# power.net
KiCad netlist of a schematic drawn in Altium Designer
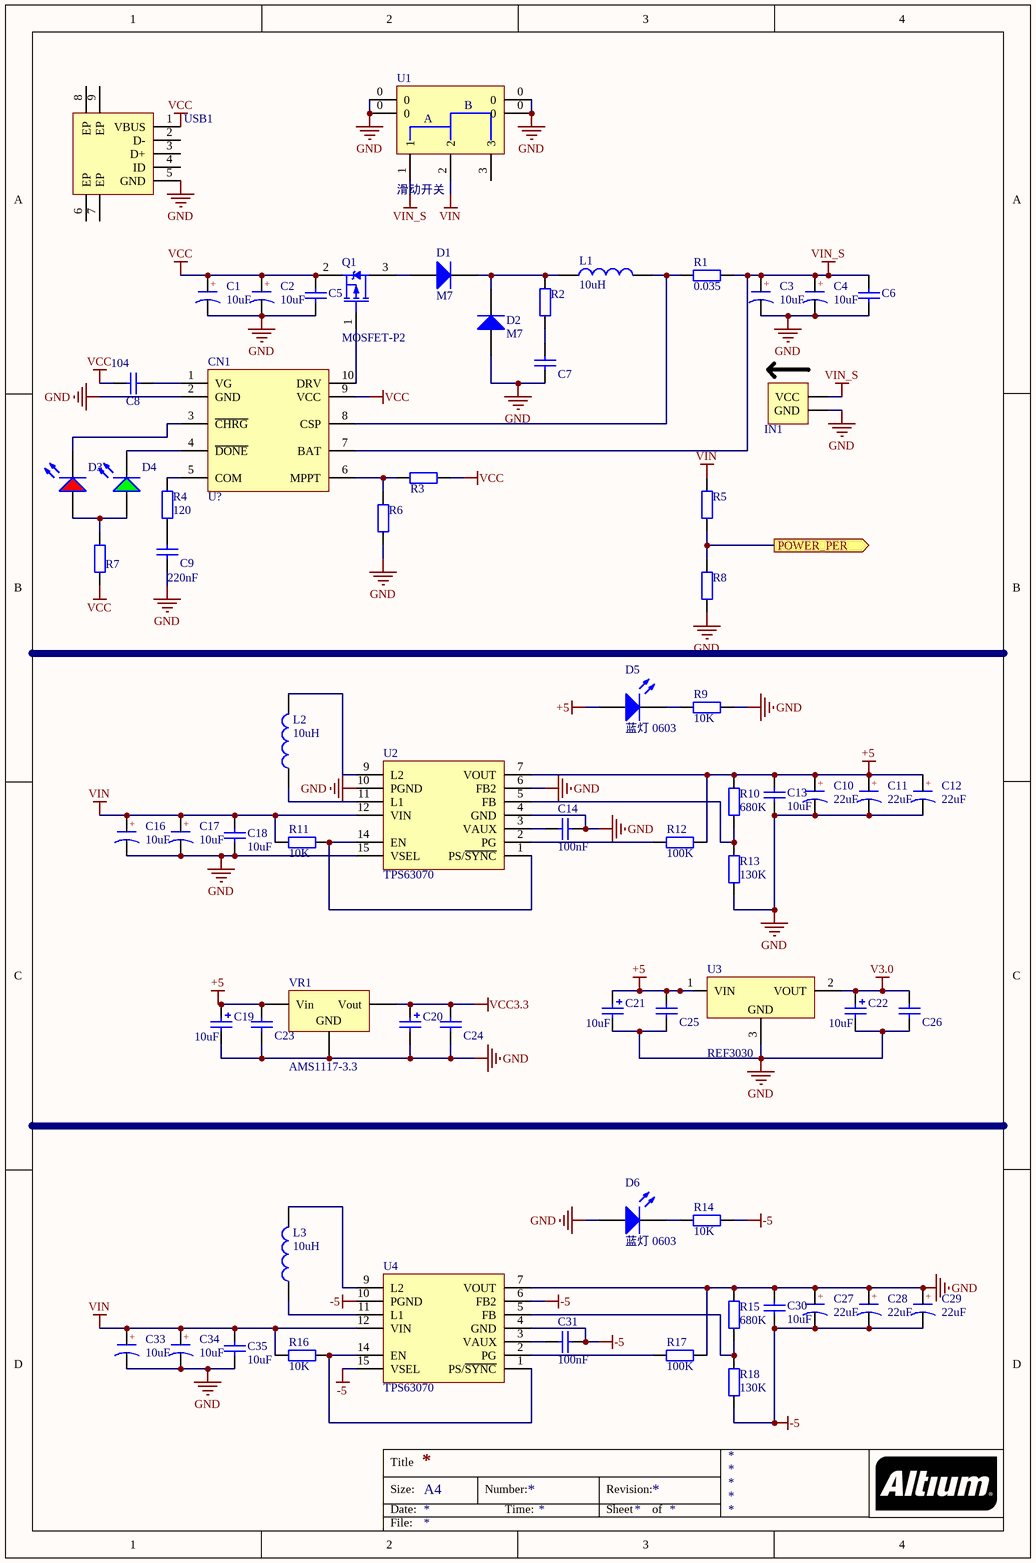
[diagram p0: power.SchDoc]

(export (version "E")
  (design (tool "Eeschema 10.0.6"))
  (components
    (comp (ref "C1")
      (value "10uF")
      (footprint "226C")
      (description "贴片钽电容")
      (fields (field (name "Comment") "CAP+"))
      (libsource (lib "Cooperation") (part "0CAP+"))
    )
    (comp (ref "C2")
      (value "10uF")
      (footprint "226C")
      (description "贴片钽电容")
      (fields (field (name "Comment") "CAP+"))
      (libsource (lib "Cooperation") (part "0CAP+"))
    )
    (comp (ref "C3")
      (value "10uF")
      (footprint "226C")
      (description "贴片钽电容")
      (fields (field (name "Comment") "CAP+"))
      (libsource (lib "Cooperation") (part "0CAP+"))
    )
    (comp (ref "C4")
      (value "10uF")
      (footprint "226C")
      (description "贴片钽电容")
      (fields (field (name "Comment") "CAP+"))
      (libsource (lib "Cooperation") (part "0CAP+"))
    )
    (comp (ref "C5")
      (value "10nF (103) 10% 50V")
      (footprint "0603_C")
      (description "贴片电容")
      (libsource (lib "JLC") (part "0603 10nF (103) 10% 50V"))
    )
    (comp (ref "C6")
      (value "10nF (103) 10% 50V")
      (footprint "0603_C")
      (description "贴片电容")
      (libsource (lib "JLC") (part "0603 10nF (103) 10% 50V"))
    )
    (comp (ref "C7")
      (value "10nF (103) 10% 50V")
      (footprint "0603_C")
      (description "贴片电容")
      (libsource (lib "JLC") (part "0603 10nF (103) 10% 50V"))
    )
    (comp (ref "C8")
      (value "104")
      (footprint "0603_C")
      (description "贴片电容")
      (libsource (lib "JLC") (part "0603 10nF (103) 10% 50V"))
    )
    (comp (ref "C9")
      (value "220nF")
      (footprint "0603_C")
      (description "贴片电容")
      (libsource (lib "JLC") (part "0603 10nF (103) 10% 50V"))
    )
    (comp (ref "C10")
      (value "22uF")
      (footprint "226C")
      (description "贴片钽电容")
      (fields (field (name "Comment") "CAP+"))
      (libsource (lib "Cooperation") (part "0CAP+"))
    )
    (comp (ref "C11")
      (value "22uF")
      (footprint "226C")
      (description "贴片钽电容")
      (fields (field (name "Comment") "CAP+"))
      (libsource (lib "Cooperation") (part "0CAP+"))
    )
    (comp (ref "C12")
      (value "22uF")
      (footprint "226C")
      (description "贴片钽电容")
      (fields (field (name "Comment") "CAP+"))
      (libsource (lib "Cooperation") (part "0CAP+"))
    )
    (comp (ref "C13")
      (value "10uF")
      (footprint "0603_C")
      (description "贴片电容")
      (libsource (lib "JLC") (part "0603 10uF (106) 10% 10V"))
    )
    (comp (ref "C14")
      (value "100nF")
      (footprint "0603_C")
      (description "贴片电容")
      (libsource (lib "JLC") (part "0603 10uF (106) 10% 10V"))
    )
    (comp (ref "C16")
      (value "10uF")
      (footprint "226C")
      (description "贴片钽电容")
      (fields (field (name "Comment") "CAP+"))
      (libsource (lib "Cooperation") (part "0CAP+"))
    )
    (comp (ref "C17")
      (value "10uF")
      (footprint "226C")
      (description "贴片钽电容")
      (fields (field (name "Comment") "CAP+"))
      (libsource (lib "Cooperation") (part "0CAP+"))
    )
    (comp (ref "C18")
      (value "10uF")
      (footprint "0603_C")
      (description "贴片电容")
      (libsource (lib "JLC") (part "0603 10uF (106) 10% 10V"))
    )
    (comp (ref "C19")
      (value "10uF")
      (footprint "CASE-A_3216")
      (description "钽电容")
      (libsource (lib "JLC") (part "3216 10uF (106) 10% 16V"))
    )
    (comp (ref "C20")
      (value "10uF (106) ±10% 16V")
      (footprint "CASE-A_3216")
      (description "钽电容")
      (libsource (lib "JLC") (part "3216 10uF (106) 10% 16V"))
    )
    (comp (ref "C21")
      (value "10uF")
      (footprint "CASE-A_3216")
      (description "钽电容")
      (libsource (lib "JLC") (part "3216 10uF (106) 10% 16V"))
    )
    (comp (ref "C22")
      (value "10uF")
      (footprint "CASE-A_3216")
      (description "钽电容")
      (libsource (lib "JLC") (part "3216 10uF (106) 10% 16V"))
    )
    (comp (ref "C23")
      (value "100nF (104) 10% 50V")
      (footprint "0603_C")
      (description "贴片电容")
      (libsource (lib "JLC") (part "0603 100nF (104) 10% 50V"))
    )
    (comp (ref "C24")
      (value "100nF (104) 10% 50V")
      (footprint "0603_C")
      (description "贴片电容")
      (libsource (lib "JLC") (part "0603 100nF (104) 10% 50V"))
    )
    (comp (ref "C25")
      (value "100nF (104) 10% 50V")
      (footprint "0603_C")
      (description "贴片电容")
      (libsource (lib "JLC") (part "0603 100nF (104) 10% 50V"))
    )
    (comp (ref "C26")
      (value "100nF (104) 10% 50V")
      (footprint "0603_C")
      (description "贴片电容")
      (libsource (lib "JLC") (part "0603 100nF (104) 10% 50V"))
    )
    (comp (ref "C27")
      (value "22uF")
      (footprint "226C")
      (description "贴片钽电容")
      (fields (field (name "Comment") "CAP+"))
      (libsource (lib "Cooperation") (part "0CAP+"))
    )
    (comp (ref "C28")
      (value "22uF")
      (footprint "226C")
      (description "贴片钽电容")
      (fields (field (name "Comment") "CAP+"))
      (libsource (lib "Cooperation") (part "0CAP+"))
    )
    (comp (ref "C29")
      (value "22uF")
      (footprint "226C")
      (description "贴片钽电容")
      (fields (field (name "Comment") "CAP+"))
      (libsource (lib "Cooperation") (part "0CAP+"))
    )
    (comp (ref "C30")
      (value "10uF")
      (footprint "0603_C")
      (description "贴片电容")
      (libsource (lib "JLC") (part "0603 10uF (106) 10% 10V"))
    )
    (comp (ref "C31")
      (value "100nF")
      (footprint "0603_C")
      (description "贴片电容")
      (libsource (lib "JLC") (part "0603 10uF (106) 10% 10V"))
    )
    (comp (ref "C33")
      (value "10uF")
      (footprint "226C")
      (description "贴片钽电容")
      (fields (field (name "Comment") "CAP+"))
      (libsource (lib "Cooperation") (part "0CAP+"))
    )
    (comp (ref "C34")
      (value "10uF")
      (footprint "226C")
      (description "贴片钽电容")
      (fields (field (name "Comment") "CAP+"))
      (libsource (lib "Cooperation") (part "0CAP+"))
    )
    (comp (ref "C35")
      (value "10uF")
      (footprint "0603_C")
      (description "贴片电容")
      (libsource (lib "JLC") (part "0603 10uF (106) 10% 10V"))
    )
    (comp (ref "CN1") (value "U?") (footprint "SSOP_10") (libsource (lib "Cooperation") (part "CN3791")))
    (comp (ref "D1")
      (value "M7")
      (footprint "SMA(DO-214AC)_S1")
      (description "二极管")
      (libsource (lib "JLC") (part "SMA(DO-214AC) M7"))
    )
    (comp (ref "D2")
      (value "M7")
      (footprint "SMA(DO-214AC)_S1")
      (description "二极管")
      (libsource (lib "JLC") (part "SMA(DO-214AC) M7"))
    )
    (comp (ref "D3")
      (value "红灯 0603")
      (footprint "0603_LED_S1")
      (description "发光二极管")
      (libsource (lib "JLC") (part "0603 红灯"))
    )
    (comp (ref "D4")
      (value "绿灯 0603")
      (footprint "0603_LED_S1")
      (description "发光二极管")
      (libsource (lib "JLC") (part "0603 绿灯"))
    )
    (comp (ref "D5")
      (value "蓝灯 0603")
      (footprint "0603_LED_S1")
      (description "发光二极管")
      (libsource (lib "JLC") (part "0603 蓝灯"))
    )
    (comp (ref "D6")
      (value "蓝灯 0603")
      (footprint "0603_LED_S1")
      (description "发光二极管")
      (libsource (lib "JLC") (part "0603 蓝灯"))
    )
    (comp (ref "IN1")
      (value "HDR-1X2")
      (footprint "Power_IN_3.81-2P")
      (description "2P接插件,模块单电源供电口")
      (fields (field (name "版权归属") "源创客"))
      (libsource (lib "Cooperation") (part "PORT_Power_IN2"))
    )
    (comp (ref "L1")
      (value "10uH")
      (footprint "L8*8*4")
      (description "小功率贴片电感")
      (fields (field (name "Comment") "IND"))
      (libsource (lib "Cooperation") (part "0IND"))
    )
    (comp (ref "L2")
      (value "10uH")
      (footprint "L_6*6*2")
      (description "小功率贴片电感")
      (fields (field (name "Comment") "IND"))
      (libsource (lib "Cooperation") (part "0IND"))
    )
    (comp (ref "L3")
      (value "10uH")
      (footprint "L_6*6*2")
      (description "小功率贴片电感")
      (fields (field (name "Comment") "IND"))
      (libsource (lib "Cooperation") (part "0IND"))
    )
    (comp (ref "Q1")
      (value "MOSFET-P2")
      (footprint "SOT23-3M")
      (description "P-Channel MOSFET")
      (fields (field (name "PUBLISHER") "Altium Limited"))
      (libsource (lib "Cooperation") (part "MOS_MOSFET-P2"))
    )
    (comp (ref "R1")
      (value "0.035")
      (footprint "R 2512_L")
      (description "贴片电阻")
      (libsource (lib "") (part "0603 100Ω (1000) 1%_1"))
    )
    (comp (ref "R2")
      (value "100Ω (1000) ±1%")
      (footprint "0603_R")
      (description "贴片电阻")
      (libsource (lib "JLC") (part "0603 100Ω (1000) 1%"))
    )
    (comp (ref "R3")
      (value "100Ω (1000) ±1%")
      (footprint "0603_R")
      (description "贴片电阻")
      (libsource (lib "") (part "0603 100Ω (1000) 1%_1"))
    )
    (comp (ref "R4")
      (value "120")
      (footprint "0603_R")
      (description "贴片电阻")
      (libsource (lib "JLC") (part "0603 100Ω (1000) 1%"))
    )
    (comp (ref "R5")
      (value "100Ω (1000) ±1%")
      (footprint "0603_R")
      (description "贴片电阻")
      (libsource (lib "JLC") (part "0603 100Ω (1000) 1%"))
    )
    (comp (ref "R6")
      (value "100Ω (1000) ±1%")
      (footprint "0603_R")
      (description "贴片电阻")
      (libsource (lib "JLC") (part "0603 100Ω (1000) 1%"))
    )
    (comp (ref "R7")
      (value "100Ω (1000) ±1%")
      (footprint "0603_R")
      (description "贴片电阻")
      (libsource (lib "") (part "0603 100Ω (1000) 1%_2"))
    )
    (comp (ref "R8")
      (value "100Ω (1000) ±1%")
      (footprint "0603_R")
      (description "贴片电阻")
      (libsource (lib "JLC") (part "0603 100Ω (1000) 1%"))
    )
    (comp (ref "R9")
      (value "10K")
      (footprint "0603_R")
      (description "贴片电阻")
      (libsource (lib "JLC") (part "0603 1.2KΩ (1201) 1%"))
    )
    (comp (ref "R10")
      (value "680K")
      (footprint "0603_R")
      (description "贴片电阻")
      (libsource (lib "") (part "0603 1.2KΩ (1201) 1%_1"))
    )
    (comp (ref "R11")
      (value "10K")
      (footprint "0603_R")
      (description "贴片电阻")
      (libsource (lib "JLC") (part "0603 1.2KΩ (1201) 1%"))
    )
    (comp (ref "R12")
      (value "100K")
      (footprint "0603_R")
      (description "贴片电阻")
      (libsource (lib "") (part "0603 1.2KΩ (1201) 1%_2"))
    )
    (comp (ref "R13")
      (value "130K")
      (footprint "0603_R")
      (description "贴片电阻")
      (libsource (lib "") (part "0603 1.2KΩ (1201) 1%_1"))
    )
    (comp (ref "R14")
      (value "10K")
      (footprint "0603_R")
      (description "贴片电阻")
      (libsource (lib "JLC") (part "0603 1.2KΩ (1201) 1%"))
    )
    (comp (ref "R15")
      (value "680K")
      (footprint "0603_R")
      (description "贴片电阻")
      (libsource (lib "") (part "0603 1.2KΩ (1201) 1%_1"))
    )
    (comp (ref "R16")
      (value "10K")
      (footprint "0603_R")
      (description "贴片电阻")
      (libsource (lib "JLC") (part "0603 1.2KΩ (1201) 1%"))
    )
    (comp (ref "R17")
      (value "100K")
      (footprint "0603_R")
      (description "贴片电阻")
      (libsource (lib "") (part "0603 1.2KΩ (1201) 1%_2"))
    )
    (comp (ref "R18")
      (value "130K")
      (footprint "0603_R")
      (description "贴片电阻")
      (libsource (lib "") (part "0603 1.2KΩ (1201) 1%_1"))
    )
    (comp (ref "U1")
      (value "滑动开关")
      (footprint "SW-SMD_3P-L6.6-W2.7-P1.50 - duplicate")
      (libsource (lib "Cooperation") (part "TA_6.6*2.7*2.5_滑动开关"))
    )
    (comp (ref "U2")
      (value "TPS63070")
      (footprint "TPS63070")
      (libsource (lib "Cooperation") (part "TPS63070"))
    )
    (comp (ref "U3")
      (value "REF3030")
      (footprint "SOT23-3N")
      (libsource (lib "Cooperation") (part "REF3040"))
    )
    (comp (ref "U4")
      (value "TPS63070")
      (footprint "TPS63070")
      (libsource (lib "Cooperation") (part "TPS63070"))
    )
    (comp (ref "USB1")
      (value "PORT_micro-5P破板式")
      (footprint "micro-5P破板式")
      (libsource (lib "Cooperation") (part "PORT_micro-5P破板式"))
    )
    (comp (ref "VR1")
      (value "AMS1117-3.3")
      (footprint "SOT-223")
      (description "低压差线性稳压(LDO)")
      (libsource (lib "JLC") (part "SOT-223 AMS1117-3.3"))
    )
  )
  (nets
    (net (code "1") (name "+5") (class "Default")
      (node (ref "C10") (pin "1") (pinfunction "A_1") (pintype "passive"))
      (node (ref "C11") (pin "1") (pinfunction "A_1") (pintype "passive"))
      (node (ref "C12") (pin "1") (pinfunction "A_1") (pintype "passive"))
      (node (ref "C13") (pin "2") (pinfunction "2_2") (pintype "passive"))
      (node (ref "C19") (pin "1") (pinfunction "1_1") (pintype "passive"))
      (node (ref "C21") (pin "1") (pinfunction "1_1") (pintype "passive"))
      (node (ref "C23") (pin "1") (pinfunction "1_1") (pintype "passive"))
      (node (ref "C25") (pin "1") (pinfunction "1_1") (pintype "passive"))
      (node (ref "D5") (pin "A") (pinfunction "A_A") (pintype "passive"))
      (node (ref "R10") (pin "2") (pinfunction "2_2") (pintype "passive"))
      (node (ref "R12") (pin "1") (pinfunction "1_1") (pintype "passive"))
      (node (ref "U2") (pin "7") (pinfunction "VOUT_7") (pintype "passive"))
      (node (ref "U3") (pin "1") (pinfunction "VIN_1") (pintype "passive"))
      (node (ref "VR1") (pin "3") (pinfunction "Vin_3") (pintype "passive"))
    )
    (net (code "2") (name "-5") (class "Default")
      (node (ref "C27") (pin "2") (pinfunction "K_2") (pintype "passive"))
      (node (ref "C28") (pin "2") (pinfunction "K_2") (pintype "passive"))
      (node (ref "C29") (pin "2") (pinfunction "K_2") (pintype "passive"))
      (node (ref "C30") (pin "1") (pinfunction "1_1") (pintype "passive"))
      (node (ref "C31") (pin "1") (pinfunction "1_1") (pintype "passive"))
      (node (ref "R14") (pin "2") (pinfunction "2_2") (pintype "passive"))
      (node (ref "R18") (pin "1") (pinfunction "1_1") (pintype "passive"))
      (node (ref "U4") (pin "10") (pinfunction "PGND_10") (pintype "passive"))
      (node (ref "U4") (pin "15") (pinfunction "VSEL_15") (pintype "passive"))
      (node (ref "U4") (pin "4") (pinfunction "GND_4") (pintype "passive"))
      (node (ref "U4") (pin "6") (pinfunction "FB2_6") (pintype "passive"))
    )
    (net (code "3") (name "/POWER_PER") (class "Default")
      (node (ref "R5") (pin "1") (pinfunction "1_1") (pintype "passive"))
      (node (ref "R8") (pin "2") (pinfunction "2_2") (pintype "passive"))
    )
    (net (code "4") (name "GND") (class "Default")
      (node (ref "C1") (pin "2") (pinfunction "K_2") (pintype "passive"))
      (node (ref "C10") (pin "2") (pinfunction "K_2") (pintype "passive"))
      (node (ref "C11") (pin "2") (pinfunction "K_2") (pintype "passive"))
      (node (ref "C12") (pin "2") (pinfunction "K_2") (pintype "passive"))
      (node (ref "C13") (pin "1") (pinfunction "1_1") (pintype "passive"))
      (node (ref "C14") (pin "1") (pinfunction "1_1") (pintype "passive"))
      (node (ref "C16") (pin "2") (pinfunction "K_2") (pintype "passive"))
      (node (ref "C17") (pin "2") (pinfunction "K_2") (pintype "passive"))
      (node (ref "C18") (pin "1") (pinfunction "1_1") (pintype "passive"))
      (node (ref "C19") (pin "2") (pinfunction "2_2") (pintype "passive"))
      (node (ref "C2") (pin "2") (pinfunction "K_2") (pintype "passive"))
      (node (ref "C20") (pin "2") (pinfunction "2_2") (pintype "passive"))
      (node (ref "C21") (pin "2") (pinfunction "2_2") (pintype "passive"))
      (node (ref "C22") (pin "2") (pinfunction "2_2") (pintype "passive"))
      (node (ref "C23") (pin "2") (pinfunction "2_2") (pintype "passive"))
      (node (ref "C24") (pin "2") (pinfunction "2_2") (pintype "passive"))
      (node (ref "C25") (pin "2") (pinfunction "2_2") (pintype "passive"))
      (node (ref "C26") (pin "2") (pinfunction "2_2") (pintype "passive"))
      (node (ref "C27") (pin "1") (pinfunction "A_1") (pintype "passive"))
      (node (ref "C28") (pin "1") (pinfunction "A_1") (pintype "passive"))
      (node (ref "C29") (pin "1") (pinfunction "A_1") (pintype "passive"))
      (node (ref "C3") (pin "2") (pinfunction "K_2") (pintype "passive"))
      (node (ref "C30") (pin "2") (pinfunction "2_2") (pintype "passive"))
      (node (ref "C33") (pin "2") (pinfunction "K_2") (pintype "passive"))
      (node (ref "C34") (pin "2") (pinfunction "K_2") (pintype "passive"))
      (node (ref "C35") (pin "1") (pinfunction "1_1") (pintype "passive"))
      (node (ref "C4") (pin "2") (pinfunction "K_2") (pintype "passive"))
      (node (ref "C5") (pin "1") (pinfunction "1_1") (pintype "passive"))
      (node (ref "C6") (pin "1") (pinfunction "1_1") (pintype "passive"))
      (node (ref "C7") (pin "2") (pinfunction "2_2") (pintype "passive"))
      (node (ref "C9") (pin "2") (pinfunction "2_2") (pintype "passive"))
      (node (ref "CN1") (pin "2") (pinfunction "GND_2") (pintype "passive"))
      (node (ref "D2") (pin "1") (pinfunction "A_1") (pintype "passive"))
      (node (ref "D6") (pin "A") (pinfunction "A_A") (pintype "passive"))
      (node (ref "IN1") (pin "2") (pinfunction "GND_2") (pintype "passive"))
      (node (ref "R13") (pin "1") (pinfunction "1_1") (pintype "passive"))
      (node (ref "R15") (pin "2") (pinfunction "2_2") (pintype "passive"))
      (node (ref "R17") (pin "1") (pinfunction "1_1") (pintype "passive"))
      (node (ref "R6") (pin "1") (pinfunction "1_1") (pintype "passive"))
      (node (ref "R8") (pin "1") (pinfunction "1_1") (pintype "passive"))
      (node (ref "R9") (pin "2") (pinfunction "2_2") (pintype "passive"))
      (node (ref "U1") (pin "0") (pinfunction "0_0") (pintype "passive"))
      (node (ref "U2") (pin "10") (pinfunction "PGND_10") (pintype "passive"))
      (node (ref "U2") (pin "15") (pinfunction "VSEL_15") (pintype "passive"))
      (node (ref "U2") (pin "4") (pinfunction "GND_4") (pintype "passive"))
      (node (ref "U2") (pin "6") (pinfunction "FB2_6") (pintype "passive"))
      (node (ref "U3") (pin "3") (pinfunction "GND_3") (pintype "passive"))
      (node (ref "U4") (pin "7") (pinfunction "VOUT_7") (pintype "passive"))
      (node (ref "USB1") (pin "5") (pinfunction "GND_5") (pintype "passive"))
      (node (ref "VR1") (pin "1") (pinfunction "GND_1") (pintype "passive"))
    )
    (net (code "5") (name "Net-(C7-Pad1)") (class "Default")
      (node (ref "C7") (pin "1") (pinfunction "1_1") (pintype "passive"))
      (node (ref "R2") (pin "1") (pinfunction "1_1") (pintype "passive"))
    )
    (net (code "6") (name "Net-(C9-Pad1)") (class "Default")
      (node (ref "C9") (pin "1") (pinfunction "1_1") (pintype "passive"))
      (node (ref "R4") (pin "1") (pinfunction "1_1") (pintype "passive"))
    )
    (net (code "7") (name "Net-(CN1-COM)") (class "Default")
      (node (ref "CN1") (pin "5") (pinfunction "COM_5") (pintype "passive"))
      (node (ref "R4") (pin "2") (pinfunction "2_2") (pintype "passive"))
    )
    (net (code "8") (name "Net-(CN1-CSP)") (class "Default")
      (node (ref "CN1") (pin "8") (pinfunction "CSP_8") (pintype "passive"))
      (node (ref "L1") (pin "2") (pinfunction "2_2") (pintype "passive"))
      (node (ref "R1") (pin "2") (pinfunction "2_2") (pintype "passive"))
    )
    (net (code "9") (name "Net-(CN1-DRV)") (class "Default")
      (node (ref "CN1") (pin "10") (pinfunction "DRV_10") (pintype "passive"))
      (node (ref "Q1") (pin "1") (pinfunction "G_1") (pintype "passive"))
    )
    (net (code "10") (name "Net-(CN1-MPPT)") (class "Default")
      (node (ref "CN1") (pin "6") (pinfunction "MPPT_6") (pintype "passive"))
      (node (ref "R3") (pin "2") (pinfunction "2_2") (pintype "passive"))
      (node (ref "R6") (pin "2") (pinfunction "2_2") (pintype "passive"))
    )
    (net (code "11") (name "Net-(CN1-VG)") (class "Default")
      (node (ref "C8") (pin "1") (pinfunction "1_1") (pintype "passive"))
      (node (ref "CN1") (pin "1") (pinfunction "VG_1") (pintype "passive"))
    )
    (net (code "12") (name "Net-(CN1-~{CHRG})") (class "Default")
      (node (ref "CN1") (pin "3") (pinfunction "~{CHRG}_3") (pintype "passive"))
      (node (ref "D3") (pin "K") (pinfunction "K_K") (pintype "passive"))
    )
    (net (code "13") (name "Net-(CN1-~{DONE})") (class "Default")
      (node (ref "CN1") (pin "4") (pinfunction "~{DONE}_4") (pintype "passive"))
      (node (ref "D4") (pin "K") (pinfunction "K_K") (pintype "passive"))
    )
    (net (code "14") (name "Net-(D1-A)") (class "Default")
      (node (ref "D1") (pin "1") (pinfunction "A_1") (pintype "passive"))
      (node (ref "Q1") (pin "3") (pinfunction "D_3") (pintype "passive"))
    )
    (net (code "15") (name "Net-(D1-K)") (class "Default")
      (node (ref "D1") (pin "2") (pinfunction "K_2") (pintype "passive"))
      (node (ref "D2") (pin "2") (pinfunction "K_2") (pintype "passive"))
      (node (ref "L1") (pin "1") (pinfunction "1_1") (pintype "passive"))
      (node (ref "R2") (pin "2") (pinfunction "2_2") (pintype "passive"))
    )
    (net (code "16") (name "Net-(D3-PadA)") (class "Default")
      (node (ref "D3") (pin "A") (pinfunction "A_A") (pintype "passive"))
      (node (ref "D4") (pin "A") (pinfunction "A_A") (pintype "passive"))
      (node (ref "R7") (pin "1") (pinfunction "1_1") (pintype "passive"))
    )
    (net (code "17") (name "Net-(D5-PadK)") (class "Default")
      (node (ref "D5") (pin "K") (pinfunction "K_K") (pintype "passive"))
      (node (ref "R9") (pin "1") (pinfunction "1_1") (pintype "passive"))
    )
    (net (code "18") (name "Net-(D6-PadK)") (class "Default")
      (node (ref "D6") (pin "K") (pinfunction "K_K") (pintype "passive"))
      (node (ref "R14") (pin "1") (pinfunction "1_1") (pintype "passive"))
    )
    (net (code "19") (name "Net-(U2-EN)") (class "Default")
      (node (ref "R11") (pin "2") (pinfunction "2_2") (pintype "passive"))
      (node (ref "U2") (pin "1") (pinfunction "PS/~{SYNC}_1") (pintype "passive"))
      (node (ref "U2") (pin "14") (pinfunction "EN_14") (pintype "passive"))
    )
    (net (code "20") (name "Net-(U2-FB)") (class "Default")
      (node (ref "R10") (pin "1") (pinfunction "1_1") (pintype "passive"))
      (node (ref "R13") (pin "2") (pinfunction "2_2") (pintype "passive"))
      (node (ref "U2") (pin "5") (pinfunction "FB_5") (pintype "passive"))
    )
    (net (code "21") (name "Net-(U2-L1)") (class "Default")
      (node (ref "L2") (pin "1") (pinfunction "1_1") (pintype "passive"))
      (node (ref "U2") (pin "11") (pinfunction "L1_11") (pintype "passive"))
    )
    (net (code "22") (name "Net-(U2-L2)") (class "Default")
      (node (ref "L2") (pin "2") (pinfunction "2_2") (pintype "passive"))
      (node (ref "U2") (pin "9") (pinfunction "L2_9") (pintype "passive"))
    )
    (net (code "23") (name "Net-(U2-PG)") (class "Default")
      (node (ref "R12") (pin "2") (pinfunction "2_2") (pintype "passive"))
      (node (ref "U2") (pin "2") (pinfunction "PG_2") (pintype "passive"))
    )
    (net (code "24") (name "Net-(U2-VAUX)") (class "Default")
      (node (ref "C14") (pin "2") (pinfunction "2_2") (pintype "passive"))
      (node (ref "U2") (pin "3") (pinfunction "VAUX_3") (pintype "passive"))
    )
    (net (code "25") (name "Net-(U4-EN)") (class "Default")
      (node (ref "R16") (pin "2") (pinfunction "2_2") (pintype "passive"))
      (node (ref "U4") (pin "1") (pinfunction "PS/~{SYNC}_1") (pintype "passive"))
      (node (ref "U4") (pin "14") (pinfunction "EN_14") (pintype "passive"))
    )
    (net (code "26") (name "Net-(U4-FB)") (class "Default")
      (node (ref "R15") (pin "1") (pinfunction "1_1") (pintype "passive"))
      (node (ref "R18") (pin "2") (pinfunction "2_2") (pintype "passive"))
      (node (ref "U4") (pin "5") (pinfunction "FB_5") (pintype "passive"))
    )
    (net (code "27") (name "Net-(U4-L1)") (class "Default")
      (node (ref "L3") (pin "1") (pinfunction "1_1") (pintype "passive"))
      (node (ref "U4") (pin "11") (pinfunction "L1_11") (pintype "passive"))
    )
    (net (code "28") (name "Net-(U4-L2)") (class "Default")
      (node (ref "L3") (pin "2") (pinfunction "2_2") (pintype "passive"))
      (node (ref "U4") (pin "9") (pinfunction "L2_9") (pintype "passive"))
    )
    (net (code "29") (name "Net-(U4-PG)") (class "Default")
      (node (ref "R17") (pin "2") (pinfunction "2_2") (pintype "passive"))
      (node (ref "U4") (pin "2") (pinfunction "PG_2") (pintype "passive"))
    )
    (net (code "30") (name "Net-(U4-VAUX)") (class "Default")
      (node (ref "C31") (pin "2") (pinfunction "2_2") (pintype "passive"))
      (node (ref "U4") (pin "3") (pinfunction "VAUX_3") (pintype "passive"))
    )
    (net (code "31") (name "V3.0") (class "Default")
      (node (ref "C22") (pin "1") (pinfunction "1_1") (pintype "passive"))
      (node (ref "C26") (pin "1") (pinfunction "1_1") (pintype "passive"))
      (node (ref "U3") (pin "2") (pinfunction "VOUT_2") (pintype "passive"))
    )
    (net (code "32") (name "VCC") (class "Default")
      (node (ref "C1") (pin "1") (pinfunction "A_1") (pintype "passive"))
      (node (ref "C2") (pin "1") (pinfunction "A_1") (pintype "passive"))
      (node (ref "C5") (pin "2") (pinfunction "2_2") (pintype "passive"))
      (node (ref "C8") (pin "2") (pinfunction "2_2") (pintype "passive"))
      (node (ref "CN1") (pin "9") (pinfunction "VCC_9") (pintype "passive"))
      (node (ref "Q1") (pin "2") (pinfunction "S_2") (pintype "passive"))
      (node (ref "R3") (pin "1") (pinfunction "1_1") (pintype "passive"))
      (node (ref "R7") (pin "2") (pinfunction "2_2") (pintype "passive"))
      (node (ref "USB1") (pin "1") (pinfunction "VBUS_1") (pintype "passive"))
    )
    (net (code "33") (name "VCC3.3") (class "Default")
      (node (ref "C20") (pin "1") (pinfunction "1_1") (pintype "passive"))
      (node (ref "C24") (pin "1") (pinfunction "1_1") (pintype "passive"))
      (node (ref "VR1") (pin "2") (pinfunction "Vout_2") (pintype "passive"))
    )
    (net (code "34") (name "VIN") (class "Default")
      (node (ref "C16") (pin "1") (pinfunction "A_1") (pintype "passive"))
      (node (ref "C17") (pin "1") (pinfunction "A_1") (pintype "passive"))
      (node (ref "C18") (pin "2") (pinfunction "2_2") (pintype "passive"))
      (node (ref "C33") (pin "1") (pinfunction "A_1") (pintype "passive"))
      (node (ref "C34") (pin "1") (pinfunction "A_1") (pintype "passive"))
      (node (ref "C35") (pin "2") (pinfunction "2_2") (pintype "passive"))
      (node (ref "R11") (pin "1") (pinfunction "1_1") (pintype "passive"))
      (node (ref "R16") (pin "1") (pinfunction "1_1") (pintype "passive"))
      (node (ref "R5") (pin "2") (pinfunction "2_2") (pintype "passive"))
      (node (ref "U1") (pin "2") (pinfunction "2_2") (pintype "passive"))
      (node (ref "U2") (pin "12") (pinfunction "VIN_12") (pintype "passive"))
      (node (ref "U4") (pin "12") (pinfunction "VIN_12") (pintype "passive"))
    )
    (net (code "35") (name "VIN_S") (class "Default")
      (node (ref "C3") (pin "1") (pinfunction "A_1") (pintype "passive"))
      (node (ref "C4") (pin "1") (pinfunction "A_1") (pintype "passive"))
      (node (ref "C6") (pin "2") (pinfunction "2_2") (pintype "passive"))
      (node (ref "CN1") (pin "7") (pinfunction "BAT_7") (pintype "passive"))
      (node (ref "IN1") (pin "1") (pinfunction "VCC_1") (pintype "passive"))
      (node (ref "R1") (pin "1") (pinfunction "1_1") (pintype "passive"))
      (node (ref "U1") (pin "1") (pinfunction "1_1") (pintype "passive"))
    )
    (net (code "36") (name "unconnected-(U1-Pad3)") (class "Default")
      (node (ref "U1") (pin "3") (pinfunction "3_3") (pintype "passive"))
    )
    (net (code "37") (name "unconnected-(USB1-D+-Pad3)") (class "Default")
      (node (ref "USB1") (pin "3") (pinfunction "D+_3") (pintype "passive"))
    )
    (net (code "38") (name "unconnected-(USB1-D--Pad2)") (class "Default")
      (node (ref "USB1") (pin "2") (pinfunction "D-_2") (pintype "passive"))
    )
    (net (code "39") (name "unconnected-(USB1-EP-Pad6)") (class "Default")
      (node (ref "USB1") (pin "6") (pinfunction "EP_6") (pintype "passive"))
    )
    (net (code "40") (name "unconnected-(USB1-EP-Pad7)") (class "Default")
      (node (ref "USB1") (pin "7") (pinfunction "EP_7") (pintype "passive"))
    )
    (net (code "41") (name "unconnected-(USB1-EP-Pad8)") (class "Default")
      (node (ref "USB1") (pin "8") (pinfunction "EP_8") (pintype "passive"))
    )
    (net (code "42") (name "unconnected-(USB1-EP-Pad9)") (class "Default")
      (node (ref "USB1") (pin "9") (pinfunction "EP_9") (pintype "passive"))
    )
    (net (code "43") (name "unconnected-(USB1-ID-Pad4)") (class "Default")
      (node (ref "USB1") (pin "4") (pinfunction "ID_4") (pintype "passive"))
    )
  )
)
